# veloKinoLEd.net
KiCad netlist of a schematic drawn in EAGLE
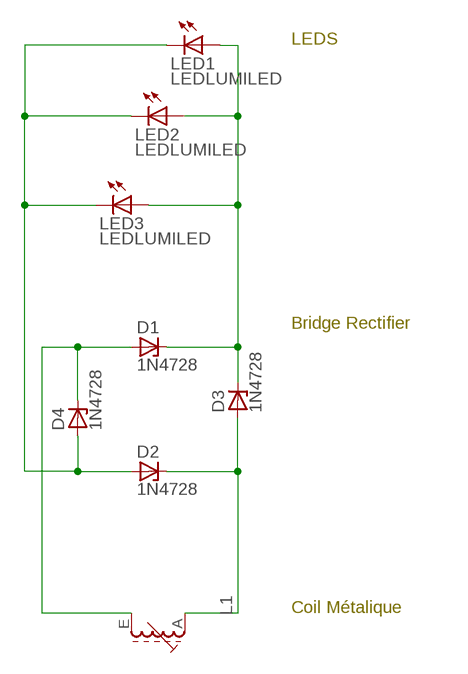
[diagram p0: schematic, sheet 1]

(export (version "E")
  (design (tool "Eeschema 10.0.6"))
  (components
    (comp (ref "D1")
      (value "1N4728")
      (footprint "eagle-import:DO41Z10")
      (libsource (lib "eagle-import") (part "1N4728"))
    )
    (comp (ref "D2")
      (value "1N4728")
      (footprint "eagle-import:DO41Z10")
      (libsource (lib "eagle-import") (part "1N4728"))
    )
    (comp (ref "D3")
      (value "1N4728")
      (footprint "eagle-import:DO41Z10")
      (libsource (lib "eagle-import") (part "1N4728"))
    )
    (comp (ref "D4")
      (value "1N4728")
      (footprint "eagle-import:DO41Z10")
      (libsource (lib "eagle-import") (part "1N4728"))
    )
    (comp (ref "L1")
      (value "71E")
      (footprint "eagle-import:71E")
      (libsource (lib "eagle-import") (part "71E"))
    )
    (comp (ref "LED1")
      (value "LEDLUMILED")
      (footprint "eagle-import:LUMILED")
      (libsource (lib "eagle-import") (part "LEDLUMILED"))
    )
    (comp (ref "LED2")
      (value "LEDLUMILED")
      (footprint "eagle-import:LUMILED")
      (libsource (lib "eagle-import") (part "LEDLUMILED"))
    )
    (comp (ref "LED3")
      (value "LEDLUMILED")
      (footprint "eagle-import:LUMILED")
      (libsource (lib "eagle-import") (part "LEDLUMILED"))
    )
  )
  (nets
    (net (code "1") (name "Net-(D1-PadA)") (class "Default")
      (node (ref "D1") (pin "A") (pinfunction "A_A") (pintype "passive"))
      (node (ref "D4") (pin "C") (pinfunction "C_C") (pintype "passive"))
      (node (ref "L1") (pin "E") (pinfunction "E_E") (pintype "passive"))
    )
    (net (code "2") (name "Net-(D2-PadC)") (class "Default")
      (node (ref "D2") (pin "C") (pinfunction "C_C") (pintype "passive"))
      (node (ref "D3") (pin "A") (pinfunction "A_A") (pintype "passive"))
      (node (ref "L1") (pin "A") (pinfunction "A_A") (pintype "passive"))
    )
    (net (code "3") (name "Net-(LED1-A)") (class "Default")
      (node (ref "D1") (pin "C") (pinfunction "C_C") (pintype "passive"))
      (node (ref "D3") (pin "C") (pinfunction "C_C") (pintype "passive"))
      (node (ref "LED1") (pin "2+") (pinfunction "A_2+") (pintype "passive"))
      (node (ref "LED2") (pin "2+") (pinfunction "A_2+") (pintype "passive"))
      (node (ref "LED3") (pin "2+") (pinfunction "A_2+") (pintype "passive"))
    )
    (net (code "4") (name "Net-(LED1-C)") (class "Default")
      (node (ref "D2") (pin "A") (pinfunction "A_A") (pintype "passive"))
      (node (ref "D4") (pin "A") (pinfunction "A_A") (pintype "passive"))
      (node (ref "LED1") (pin "4-") (pinfunction "C_4-") (pintype "passive"))
      (node (ref "LED2") (pin "4-") (pinfunction "C_4-") (pintype "passive"))
      (node (ref "LED3") (pin "4-") (pinfunction "C_4-") (pintype "passive"))
    )
  )
)
